# Power_Supply_and_Regulation.net
KiCad netlist of a schematic drawn in Altium Designer
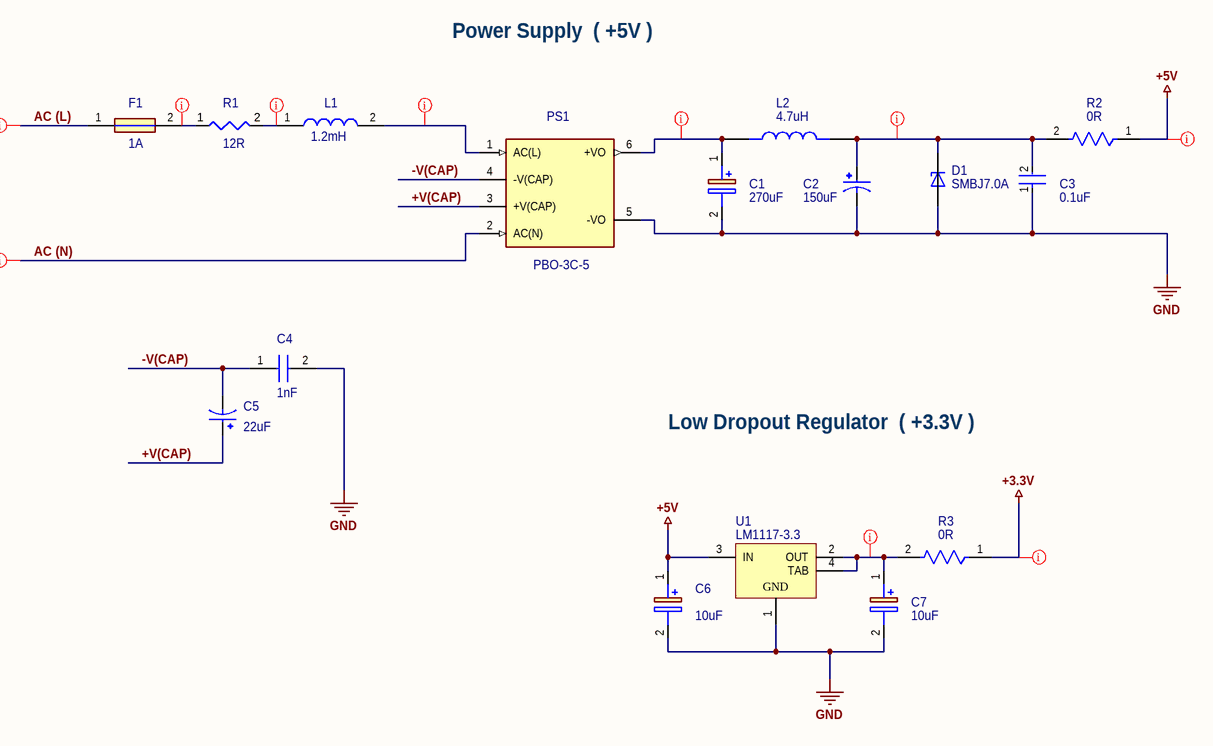
[diagram p0: Power Supply and Regulation.SchDoc]

(export (version "E")
  (design (tool "Eeschema 10.0.6"))
  (components
    (comp (ref "C1")
      (value "270uF")
      (footprint "CAPPRD250W65D630H900")
      (description "Aluminum Organic Polymer Capacitors")
      (fields
        (field (name "MANUFACTURER_PART_NUMBER") "A750EM277M1CAAE015")
        (field (name "MOUSER PART NUMBER") "667-6SEPC560MW+TSS")
      )
      (libsource (lib "SamacSys") (part "6SEPC560MW+TSS"))
    )
    (comp (ref "C2")
      (value "150uF")
      (footprint "CAPPRD500W60D800H1150")
      (description "FR-A")
      (fields (field (name "MF") "{'manufacturer': u'Panasonic'}") (field (name "MP") "UHE1V151MPD1TD"))
      (libsource (lib "SnapEDA_Library") (part "EEUFR1V221B"))
    )
    (comp (ref "C3")
      (value "0.1uF")
      (footprint "FP-CL10-0_1-MFG")
      (description "CAP CER 0.1UF 50V X7R 0603")
      (fields
        (field (name "MANUFACTURER") "Samsung Electro-Mechanics America, Inc")
        (field (name "MANUFACTURER PART NUMBER") "CL10B104JB8NNNC")
      )
      (libsource (lib "Altium Content Vault") (part "b4654b650e69147ec39a6b967a45e02"))
    )
    (comp (ref "C4")
      (value "1nF")
      (footprint "SamacSys:B32529C8102J")
      (description "Capacitor")
      (fields
        (field (name "MANUFACTURER_PART_NUMBER") "B32529C8102J")
        (field (name "MOUSER PART NUMBER") "871-B32529C8102J")
      )
      (libsource (lib "*") (part "B32529C8102J"))
    )
    (comp (ref "C5")
      (value "22uF")
      (footprint "CAPPRD750W80D1600H2500")
      (description "Aluminum Electrolytic Capacitors - Radial Leaded")
      (fields (field (name "MF") "Nichicon") (field (name "MP") "UVR2W220MHD"))
      (libsource (lib "SnapEDA_Library") (part "EEUTP1E272B"))
    )
    (comp (ref "C6")
      (value "10uF")
      (footprint "SamacSys:T491B")
      (description "Capacitor Polarised")
      (fields
        (field (name "MANUFACTURER_PART_NUMBER") "T491B106M010AT")
        (field (name "MOUSER PART NUMBER") "80-T491B106M010")
      )
      (libsource (lib "*") (part "T491B106M010AT"))
    )
    (comp (ref "C7")
      (value "10uF")
      (footprint "SamacSys:T491B")
      (description "Capacitor Polarised")
      (fields
        (field (name "MANUFACTURER_PART_NUMBER") "T491B106M010AT")
        (field (name "MOUSER PART NUMBER") "80-T491B106M010")
      )
      (libsource (lib "*") (part "T491B106M010AT"))
    )
    (comp (ref "D1")
      (value "SMBJ7.0A")
      (footprint "DIOM4336X265N")
      (fields (field (name "MF") "{'manufacturer': u'Littelfuse'}"))
      (libsource (lib "SnapEDA_Library") (part "SMBJ7.0A"))
    )
    (comp (ref "F1")
      (value "1A")
      (footprint "SS5H1AAPH")
      (description "Fuse")
      (fields
        (field (name "MOUSER PART NUMBER") "504-SS-5H-1A-APH")
        (field (name "MANUFACTURER_PART_NUMBER") "SS-5H-1A-APH")
      )
      (libsource (lib "University of Moratuwa") (part "SS-5H-1A-APH"))
    )
    (comp (ref "L1")
      (value "1.2mH")
      (footprint "SamacSys:RLB9012122KL")
      (description "Inductor")
      (fields
        (field (name "MANUFACTURER_PART_NUMBER") "RLB9012-122KL")
        (field (name "MOUSER PART NUMBER") "652-RLB9012-122KL")
      )
      (libsource (lib "*") (part "RLB9012-122KL"))
    )
    (comp (ref "L2")
      (value "4.7uH")
      (footprint "IND_ASPI-0615FS-4R7M-T2")
      (fields (field (name "MF") "{'manufacturer': u'Abracon'}") (field (name "MP") "ASPI-0615FS-4R7M-T2"))
      (libsource (lib "SnapEDA_Library") (part "ASPI-0615FS-4R7M-T2"))
    )
    (comp (ref "PS1")
      (value "PBO-3C-5")
      (footprint "CONV_PBO-3C-5")
      (fields (field (name "MF") "{'manufacturer': u'CUI'}"))
      (libsource (lib "SnapEDA_Library") (part "PBO-3C-5"))
    )
    (comp (ref "R1")
      (value "12R")
      (footprint "WA84-12RJI-Footprint-1")
      (libsource (lib "University of Moratuwa") (part "WA84-12RJI"))
    )
    (comp (ref "R2")
      (value "0R")
      (footprint "FP-RC0805-MFG")
      (description "RES SMD 0 OHM JUMPER 1/8W 0805")
      (fields
        (field (name "OCTOPART") "https://octopart.com/rc0805fr-070rl-yageo-9293404")
        (field (name "MANUFACTURER") "Yageo")
      )
      (libsource (lib "Altium Content Vault") (part "1029c3af85768c4190bb7ad29bc67b5"))
    )
    (comp (ref "R3")
      (value "0R")
      (footprint "FP-RC0805-MFG")
      (description "RES SMD 0 OHM JUMPER 1/8W 0805")
      (fields
        (field (name "OCTOPART") "https://octopart.com/rc0805fr-070rl-yageo-9293404")
        (field (name "MANUFACTURER") "Yageo")
      )
      (libsource (lib "Altium Content Vault") (part "1029c3af85768c4190bb7ad29bc67b5"))
    )
    (comp (ref "U1")
      (value "LM1117-3.3")
      (footprint "DCY0004A_L")
      (description "800mA Low-Dropout Linear Regulator, 4-pin SOT-223, Pb-Free")
      (fields
        (field (name "PARTNUMBER") "LM1117MPX-3.3/NOPB")
        (field (name "MANUFACTURER") "Texas Instruments")
      )
      (libsource (lib "Altium Content Vault") (part "PM-REG-LM1086-SOT4"))
    )
  )
  (nets
    (net (code "1") (name "+3.3V") (class "Default")
      (node (ref "R3") (pin "1") (pinfunction "1_1") (pintype "passive"))
    )
    (net (code "2") (name "+5V") (class "Default")
      (node (ref "C6") (pin "1") (pinfunction "+_1") (pintype "passive"))
      (node (ref "R2") (pin "1") (pinfunction "1_1") (pintype "passive"))
      (node (ref "U1") (pin "3") (pinfunction "IN_3") (pintype "power_in"))
    )
    (net (code "3") (name "/+V(CAP)") (class "Default")
      (node (ref "C5") (pin "P") (pinfunction "P_P") (pintype "passive"))
      (node (ref "PS1") (pin "3") (pinfunction "+V(CAP)_3") (pintype "passive"))
    )
    (net (code "4") (name "/-V(CAP)") (class "Default")
      (node (ref "C4") (pin "1") (pinfunction "1_1") (pintype "passive"))
      (node (ref "C5") (pin "N") (pinfunction "N_N") (pintype "passive"))
      (node (ref "PS1") (pin "4") (pinfunction "-V(CAP)_4") (pintype "passive"))
    )
    (net (code "5") (name "/AC (L)") (class "Default")
      (node (ref "F1") (pin "1") (pinfunction "1_1") (pintype "passive"))
    )
    (net (code "6") (name "/AC (N)") (class "Default")
      (node (ref "PS1") (pin "2") (pinfunction "AC(N)_2") (pintype "input"))
    )
    (net (code "7") (name "GND") (class "Default")
      (node (ref "C1") (pin "2") (pinfunction "-_2") (pintype "passive"))
      (node (ref "C2") (pin "N") (pinfunction "N_N") (pintype "passive"))
      (node (ref "C3") (pin "1") (pinfunction "1_1") (pintype "passive"))
      (node (ref "C4") (pin "2") (pinfunction "2_2") (pintype "passive"))
      (node (ref "C6") (pin "2") (pinfunction "-_2") (pintype "passive"))
      (node (ref "C7") (pin "2") (pinfunction "-_2") (pintype "passive"))
      (node (ref "D1") (pin "A") (pinfunction "A_A") (pintype "passive"))
      (node (ref "PS1") (pin "5") (pinfunction "-VO_5") (pintype "passive"))
      (node (ref "U1") (pin "1") (pinfunction "GND_1") (pintype "power_in"))
    )
    (net (code "8") (name "Net-(C1-+)") (class "Default")
      (node (ref "C1") (pin "1") (pinfunction "+_1") (pintype "passive"))
      (node (ref "L2") (pin "1") (pinfunction "1_1") (pintype "passive"))
      (node (ref "PS1") (pin "6") (pinfunction "+VO_6") (pintype "output"))
    )
    (net (code "9") (name "Net-(C2-PadP)") (class "Default")
      (node (ref "C2") (pin "P") (pinfunction "P_P") (pintype "passive"))
      (node (ref "C3") (pin "2") (pinfunction "2_2") (pintype "passive"))
      (node (ref "D1") (pin "C") (pinfunction "C_C") (pintype "passive"))
      (node (ref "L2") (pin "2") (pinfunction "2_2") (pintype "passive"))
      (node (ref "R2") (pin "2") (pinfunction "2_2") (pintype "passive"))
    )
    (net (code "10") (name "Net-(C7-+)") (class "Default")
      (node (ref "C7") (pin "1") (pinfunction "+_1") (pintype "passive"))
      (node (ref "R3") (pin "2") (pinfunction "2_2") (pintype "passive"))
      (node (ref "U1") (pin "2") (pinfunction "OUT_2") (pintype "power_in"))
      (node (ref "U1") (pin "4") (pinfunction "TAB_4") (pintype "power_in"))
    )
    (net (code "11") (name "Net-(F1-Pad2)") (class "Default")
      (node (ref "F1") (pin "2") (pinfunction "2_2") (pintype "passive"))
      (node (ref "R1") (pin "1") (pinfunction "1_1") (pintype "passive"))
    )
    (net (code "12") (name "Net-(L1-Pad1)") (class "Default")
      (node (ref "L1") (pin "1") (pinfunction "1_1") (pintype "passive"))
      (node (ref "R1") (pin "2") (pinfunction "2_2") (pintype "passive"))
    )
    (net (code "13") (name "Net-(PS1-AC(L))") (class "Default")
      (node (ref "L1") (pin "2") (pinfunction "2_2") (pintype "passive"))
      (node (ref "PS1") (pin "1") (pinfunction "AC(L)_1") (pintype "input"))
    )
    (net (code "14") (name "unconnected-(PS1--V(CAP)-Pad4_2)") (class "Default")
      (node (ref "PS1") (pin "4_2") (pinfunction "-V(CAP)_4_2") (pintype "passive"))
    )
    (net (code "15") (name "unconnected-(PS1--VO-Pad5_2)") (class "Default")
      (node (ref "PS1") (pin "5_2") (pinfunction "-VO_5_2") (pintype "output"))
    )
  )
)
